# Sheet2_led.net
KiCad netlist of a schematic drawn in Altium Designer
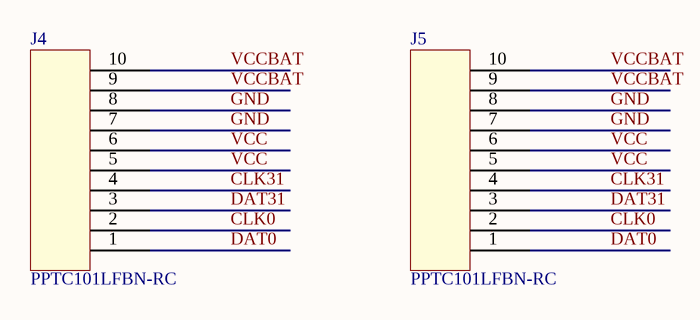
[diagram p0: Sheet2_led.SchDoc]

(export (version "E")
  (design (tool "Eeschema 10.0.6"))
  (components
    (comp (ref "J4")
      (value "PPTC101LFBN-RC")
      (footprint "PPTC101LFBN-RC")
      (description "Sullins PPTC101LFBN-RC 10 Position Header Connector 0.100\" (2.54mm) Through Hole Tin")
      (libsource (lib "lightshow") (part "PPTC101LFBN-RC"))
    )
    (comp (ref "J5")
      (value "PPTC101LFBN-RC")
      (footprint "PPTC101LFBN-RC")
      (description "Sullins PPTC101LFBN-RC 10 Position Header Connector 0.100\" (2.54mm) Through Hole Tin")
      (libsource (lib "lightshow") (part "PPTC101LFBN-RC"))
    )
  )
  (nets
    (net (code "1") (name "/CLK0") (class "Default")
      (node (ref "J4") (pin "2") (pintype "passive"))
      (node (ref "J5") (pin "2") (pintype "passive"))
    )
    (net (code "2") (name "/CLK31") (class "Default")
      (node (ref "J4") (pin "4") (pintype "passive"))
      (node (ref "J5") (pin "4") (pintype "passive"))
    )
    (net (code "3") (name "/DAT0") (class "Default")
      (node (ref "J4") (pin "1") (pintype "passive"))
      (node (ref "J5") (pin "1") (pintype "passive"))
    )
    (net (code "4") (name "/DAT31") (class "Default")
      (node (ref "J4") (pin "3") (pintype "passive"))
      (node (ref "J5") (pin "3") (pintype "passive"))
    )
    (net (code "5") (name "/GND") (class "Default")
      (node (ref "J4") (pin "7") (pintype "passive"))
      (node (ref "J4") (pin "8") (pintype "passive"))
      (node (ref "J5") (pin "7") (pintype "passive"))
      (node (ref "J5") (pin "8") (pintype "passive"))
    )
    (net (code "6") (name "/VCC") (class "Default")
      (node (ref "J4") (pin "5") (pintype "passive"))
      (node (ref "J4") (pin "6") (pintype "passive"))
      (node (ref "J5") (pin "5") (pintype "passive"))
      (node (ref "J5") (pin "6") (pintype "passive"))
    )
    (net (code "7") (name "/VCCBAT") (class "Default")
      (node (ref "J4") (pin "10") (pintype "passive"))
      (node (ref "J4") (pin "9") (pintype "passive"))
      (node (ref "J5") (pin "10") (pintype "passive"))
      (node (ref "J5") (pin "9") (pintype "passive"))
    )
  )
)
